# boost-highpower.net
KiCad netlist of a schematic drawn in EAGLE
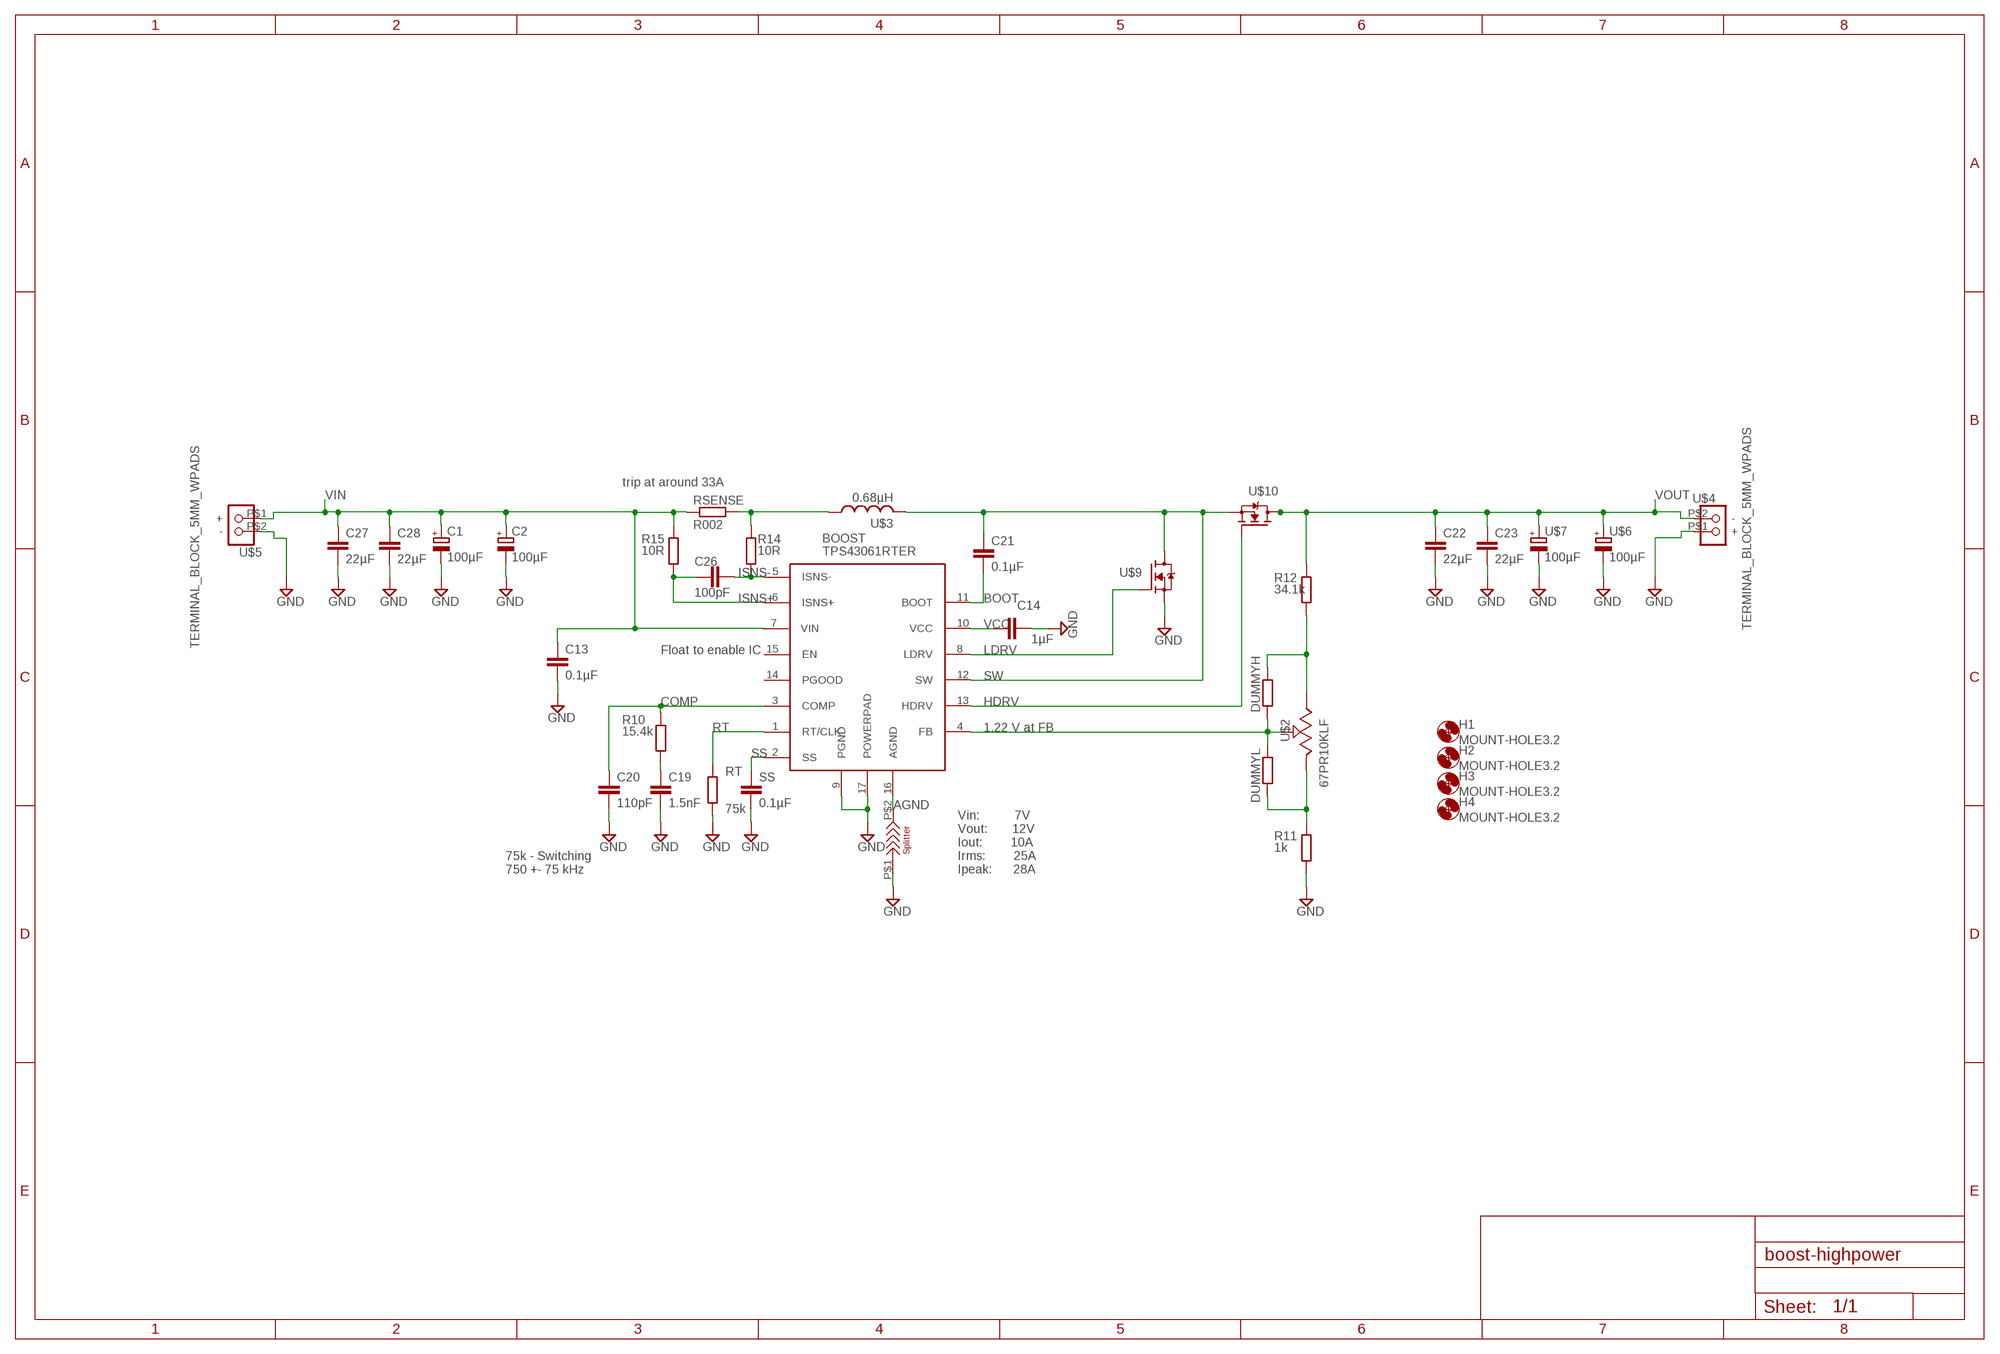
[diagram p0: schematic, sheet 1]

(export (version "E")
  (design (tool "Eeschema 10.0.6"))
  (components
    (comp (ref "BOOST")
      (value "TPS43061RTER")
      (footprint "eagle-import:QFN50P300X300X80-17N")
      (fields (field (name "MOUSER_PART_NUMBER") "595-TPS43061RTER"))
      (libsource (lib "eagle-import") (part "TPS43061RTER"))
    )
    (comp (ref "C1")
      (value "100µF")
      (footprint "eagle-import:CAPAE830X850N")
      (libsource (lib "eagle-import") (part "WCAP-ASLL-WE50V100µF"))
    )
    (comp (ref "C2")
      (value "100µF")
      (footprint "eagle-import:CAPAE830X850N")
      (libsource (lib "eagle-import") (part "WCAP-ASLL-WE50V100µF"))
    )
    (comp (ref "C13")
      (value "0.1µF")
      (footprint "eagle-import:C0805")
      (libsource (lib "eagle-import") (part "C-EUC0805"))
    )
    (comp (ref "C14")
      (value "1µF")
      (footprint "eagle-import:C0603")
      (libsource (lib "eagle-import") (part "C-EUC0603"))
    )
    (comp (ref "C19")
      (value "1.5nF")
      (footprint "eagle-import:C0603")
      (libsource (lib "eagle-import") (part "C-EUC0603"))
    )
    (comp (ref "C20")
      (value "110pF")
      (footprint "eagle-import:C0603")
      (libsource (lib "eagle-import") (part "C-EUC0603"))
    )
    (comp (ref "C21")
      (value "0.1µF")
      (footprint "eagle-import:C0805")
      (libsource (lib "eagle-import") (part "C-EUC0805"))
    )
    (comp (ref "C22")
      (value "22µF")
      (footprint "eagle-import:C0805")
      (libsource (lib "eagle-import") (part "C-EUC0805"))
    )
    (comp (ref "C23")
      (value "22µF")
      (footprint "eagle-import:C0805")
      (libsource (lib "eagle-import") (part "C-EUC0805"))
    )
    (comp (ref "C26")
      (value "100pF")
      (footprint "eagle-import:C0603")
      (libsource (lib "eagle-import") (part "C-EUC0603"))
    )
    (comp (ref "C27")
      (value "22µF")
      (footprint "eagle-import:C0805")
      (libsource (lib "eagle-import") (part "C-EUC0805"))
    )
    (comp (ref "C28")
      (value "22µF")
      (footprint "eagle-import:C0805")
      (libsource (lib "eagle-import") (part "C-EUC0805"))
    )
    (comp (ref "DUMMYH")
      (value "R-EU_R0201")
      (footprint "eagle-import:R0201")
      (libsource (lib "eagle-import") (part "R-EU_R0201"))
    )
    (comp (ref "DUMMYL")
      (value "R-EU_R0201")
      (footprint "eagle-import:R0201")
      (libsource (lib "eagle-import") (part "R-EU_R0201"))
    )
    (comp (ref "H1")
      (value "MOUNT-HOLE3.2")
      (footprint "eagle-import:3,2")
      (libsource (lib "eagle-import") (part "MOUNT-HOLE3.2"))
    )
    (comp (ref "H2")
      (value "MOUNT-HOLE3.2")
      (footprint "eagle-import:3,2")
      (libsource (lib "eagle-import") (part "MOUNT-HOLE3.2"))
    )
    (comp (ref "H3")
      (value "MOUNT-HOLE3.2")
      (footprint "eagle-import:3,2")
      (libsource (lib "eagle-import") (part "MOUNT-HOLE3.2"))
    )
    (comp (ref "H4")
      (value "MOUNT-HOLE3.2")
      (footprint "eagle-import:3,2")
      (libsource (lib "eagle-import") (part "MOUNT-HOLE3.2"))
    )
    (comp (ref "R10")
      (value "15.4k")
      (footprint "eagle-import:R0603")
      (libsource (lib "eagle-import") (part "R-EU_R0603"))
    )
    (comp (ref "R11")
      (value "1k")
      (footprint "eagle-import:R0603")
      (libsource (lib "eagle-import") (part "R-EU_R0603"))
    )
    (comp (ref "R12")
      (value "34.1k")
      (footprint "eagle-import:R0603")
      (libsource (lib "eagle-import") (part "R-EU_R0603"))
    )
    (comp (ref "R14")
      (value "10R")
      (footprint "eagle-import:R0603")
      (libsource (lib "eagle-import") (part "R-EU_R0603"))
    )
    (comp (ref "R15")
      (value "10R")
      (footprint "eagle-import:R0603")
      (libsource (lib "eagle-import") (part "R-EU_R0603"))
    )
    (comp (ref "RSENSE")
      (value "R002")
      (footprint "eagle-import:R2512W")
      (libsource (lib "eagle-import") (part "R-EU_R2512W"))
    )
    (comp (ref "RT")
      (value "75k")
      (footprint "eagle-import:R0603")
      (libsource (lib "eagle-import") (part "R-EU_R0603"))
    )
    (comp (ref "SS")
      (value "0.1µF")
      (footprint "eagle-import:C0603")
      (libsource (lib "eagle-import") (part "C-EUC0603"))
    )
    (comp (ref "U$1")
      (value "SPLITTER")
      (footprint "eagle-import:SPLITTER")
      (libsource (lib "eagle-import") (part "SPLITTER"))
    )
    (comp (ref "U$2")
      (value "67PR10KLF")
      (footprint "eagle-import:67PR10KLF")
      (libsource (lib "eagle-import") (part "67PR10KLF"))
    )
    (comp (ref "U$3")
      (value "0.68µH")
      (footprint "eagle-import:INDM135125X330N")
      (libsource (lib "eagle-import") (part "SRP1238A-XXXX"))
    )
    (comp (ref "U$4")
      (value "TERMINAL_BLOCK_5MM_WPADS")
      (footprint "eagle-import:TERMINAL_5MM_WITH_SOLDERPADS")
      (libsource (lib "eagle-import") (part "TERMINAL_BLOCK_5MM_WPADS"))
    )
    (comp (ref "U$5")
      (value "TERMINAL_BLOCK_5MM_WPADS")
      (footprint "eagle-import:TERMINAL_5MM_WITH_SOLDERPADS")
      (libsource (lib "eagle-import") (part "TERMINAL_BLOCK_5MM_WPADS"))
    )
    (comp (ref "U$6")
      (value "100µF")
      (footprint "eagle-import:CAPAE1030X1000N")
      (libsource (lib "eagle-import") (part "CAP_VZH"))
    )
    (comp (ref "U$7")
      (value "100µF")
      (footprint "eagle-import:CAPAE1030X1000N")
      (libsource (lib "eagle-import") (part "CAP_VZH"))
    )
    (comp (ref "U$9")
      (value "CSD17301Q5A")
      (footprint "eagle-import:Q5A")
      (libsource (lib "eagle-import") (part "CSD17301Q5A"))
    )
    (comp (ref "U$10")
      (value "CSD17301Q5A")
      (footprint "eagle-import:Q5A")
      (libsource (lib "eagle-import") (part "CSD17301Q5A"))
    )
  )
  (nets
    (net (code "1") (name "/AGND") (class "Default")
      (node (ref "BOOST") (pin "16") (pinfunction "AGND_16") (pintype "power_in"))
      (node (ref "U$1") (pin "P$2") (pinfunction "2_P$2") (pintype "bidirectional"))
    )
    (net (code "2") (name "/BOOT") (class "Default")
      (node (ref "BOOST") (pin "11") (pinfunction "BOOT_11") (pintype "bidirectional"))
      (node (ref "C21") (pin "2") (pinfunction "2_2") (pintype "passive"))
    )
    (net (code "3") (name "/COMP") (class "Default")
      (node (ref "BOOST") (pin "3") (pinfunction "COMP_3") (pintype "output"))
      (node (ref "C20") (pin "1") (pinfunction "1_1") (pintype "passive"))
      (node (ref "R10") (pin "2") (pinfunction "2_2") (pintype "passive"))
    )
    (net (code "4") (name "/HDRV") (class "Default")
      (node (ref "BOOST") (pin "13") (pinfunction "HDRV_13") (pintype "output"))
      (node (ref "U$10") (pin "4") (pinfunction "G_4") (pintype "passive"))
    )
    (net (code "5") (name "/ISNS+") (class "Default")
      (node (ref "BOOST") (pin "6") (pinfunction "ISNS+_6") (pintype "input"))
      (node (ref "C26") (pin "1") (pinfunction "1_1") (pintype "passive"))
      (node (ref "R15") (pin "1") (pinfunction "1_1") (pintype "passive"))
    )
    (net (code "6") (name "/ISNS-") (class "Default")
      (node (ref "BOOST") (pin "5") (pinfunction "ISNS-_5") (pintype "input"))
      (node (ref "C26") (pin "2") (pinfunction "2_2") (pintype "passive"))
      (node (ref "R14") (pin "1") (pinfunction "1_1") (pintype "passive"))
    )
    (net (code "7") (name "/LDRV") (class "Default")
      (node (ref "BOOST") (pin "8") (pinfunction "LDRV_8") (pintype "output"))
      (node (ref "U$9") (pin "4") (pinfunction "G_4") (pintype "passive"))
    )
    (net (code "8") (name "/RT") (class "Default")
      (node (ref "BOOST") (pin "1") (pinfunction "RT/CLK_1") (pintype "input"))
      (node (ref "RT") (pin "2") (pinfunction "2_2") (pintype "passive"))
    )
    (net (code "9") (name "/SS") (class "Default")
      (node (ref "BOOST") (pin "2") (pinfunction "SS_2") (pintype "bidirectional"))
      (node (ref "SS") (pin "1") (pinfunction "1_1") (pintype "passive"))
    )
    (net (code "10") (name "/SW") (class "Default")
      (node (ref "BOOST") (pin "12") (pinfunction "SW_12") (pintype "bidirectional"))
      (node (ref "C21") (pin "1") (pinfunction "1_1") (pintype "passive"))
      (node (ref "U$10") (pin "1") (pinfunction "S_1") (pintype "passive"))
      (node (ref "U$10") (pin "2") (pinfunction "S_2") (pintype "passive"))
      (node (ref "U$10") (pin "3") (pinfunction "S_3") (pintype "passive"))
      (node (ref "U$3") (pin "2") (pinfunction "2_2") (pintype "passive"))
      (node (ref "U$9") (pin "5") (pinfunction "D_5") (pintype "passive"))
      (node (ref "U$9") (pin "6") (pinfunction "D_6") (pintype "passive"))
      (node (ref "U$9") (pin "7") (pinfunction "D_7") (pintype "passive"))
      (node (ref "U$9") (pin "8") (pinfunction "D_8") (pintype "passive"))
      (node (ref "U$9") (pin "9") (pinfunction "D_9") (pintype "passive"))
    )
    (net (code "11") (name "/VCC") (class "Default")
      (node (ref "BOOST") (pin "10") (pinfunction "VCC_10") (pintype "power_in"))
      (node (ref "C14") (pin "1") (pinfunction "1_1") (pintype "passive"))
    )
    (net (code "12") (name "/VIN") (class "Default")
      (node (ref "BOOST") (pin "7") (pinfunction "VIN_7") (pintype "power_in"))
      (node (ref "C1") (pin "1") (pinfunction "+_1") (pintype "passive"))
      (node (ref "C13") (pin "1") (pinfunction "1_1") (pintype "passive"))
      (node (ref "C2") (pin "1") (pinfunction "+_1") (pintype "passive"))
      (node (ref "C27") (pin "1") (pinfunction "1_1") (pintype "passive"))
      (node (ref "C28") (pin "1") (pinfunction "1_1") (pintype "passive"))
      (node (ref "R15") (pin "2") (pinfunction "2_2") (pintype "passive"))
      (node (ref "RSENSE") (pin "1") (pinfunction "1_1") (pintype "passive"))
      (node (ref "U$5") (pin "P$1") (pinfunction "+_P$1") (pintype "bidirectional"))
    )
    (net (code "13") (name "/VOUT") (class "Default")
      (node (ref "C22") (pin "1") (pinfunction "1_1") (pintype "passive"))
      (node (ref "C23") (pin "1") (pinfunction "1_1") (pintype "passive"))
      (node (ref "R12") (pin "2") (pinfunction "2_2") (pintype "passive"))
      (node (ref "U$10") (pin "5") (pinfunction "D_5") (pintype "passive"))
      (node (ref "U$10") (pin "6") (pinfunction "D_6") (pintype "passive"))
      (node (ref "U$10") (pin "7") (pinfunction "D_7") (pintype "passive"))
      (node (ref "U$10") (pin "8") (pinfunction "D_8") (pintype "passive"))
      (node (ref "U$10") (pin "9") (pinfunction "D_9") (pintype "passive"))
      (node (ref "U$4") (pin "P$2") (pinfunction "-_P$2") (pintype "bidirectional"))
      (node (ref "U$6") (pin "1") (pinfunction "+_1") (pintype "passive"))
      (node (ref "U$7") (pin "1") (pinfunction "+_1") (pintype "passive"))
    )
    (net (code "14") (name "GND") (class "Default")
      (node (ref "BOOST") (pin "17") (pinfunction "POWERPAD_17") (pintype "power_in"))
      (node (ref "BOOST") (pin "9") (pinfunction "PGND_9") (pintype "power_in"))
      (node (ref "C1") (pin "2") (pinfunction "-_2") (pintype "passive"))
      (node (ref "C13") (pin "2") (pinfunction "2_2") (pintype "passive"))
      (node (ref "C14") (pin "2") (pinfunction "2_2") (pintype "passive"))
      (node (ref "C19") (pin "2") (pinfunction "2_2") (pintype "passive"))
      (node (ref "C2") (pin "2") (pinfunction "-_2") (pintype "passive"))
      (node (ref "C20") (pin "2") (pinfunction "2_2") (pintype "passive"))
      (node (ref "C22") (pin "2") (pinfunction "2_2") (pintype "passive"))
      (node (ref "C23") (pin "2") (pinfunction "2_2") (pintype "passive"))
      (node (ref "C27") (pin "2") (pinfunction "2_2") (pintype "passive"))
      (node (ref "C28") (pin "2") (pinfunction "2_2") (pintype "passive"))
      (node (ref "R11") (pin "1") (pinfunction "1_1") (pintype "passive"))
      (node (ref "RT") (pin "1") (pinfunction "1_1") (pintype "passive"))
      (node (ref "SS") (pin "2") (pinfunction "2_2") (pintype "passive"))
      (node (ref "U$1") (pin "P$1") (pinfunction "1_P$1") (pintype "bidirectional"))
      (node (ref "U$4") (pin "P$1") (pinfunction "+_P$1") (pintype "bidirectional"))
      (node (ref "U$5") (pin "P$2") (pinfunction "-_P$2") (pintype "bidirectional"))
      (node (ref "U$6") (pin "2") (pinfunction "-_2") (pintype "passive"))
      (node (ref "U$7") (pin "2") (pinfunction "-_2") (pintype "passive"))
      (node (ref "U$9") (pin "1") (pinfunction "S_1") (pintype "passive"))
      (node (ref "U$9") (pin "2") (pinfunction "S_2") (pintype "passive"))
      (node (ref "U$9") (pin "3") (pinfunction "S_3") (pintype "passive"))
    )
    (net (code "15") (name "Net-(BOOST-FB)") (class "Default")
      (node (ref "BOOST") (pin "4") (pinfunction "FB_4") (pintype "input"))
      (node (ref "DUMMYH") (pin "1") (pinfunction "1_1") (pintype "passive"))
      (node (ref "DUMMYL") (pin "2") (pinfunction "2_2") (pintype "passive"))
      (node (ref "U$2") (pin "P$2") (pinfunction "2_P$2") (pintype "passive"))
    )
    (net (code "16") (name "Net-(C19-Pad1)") (class "Default")
      (node (ref "C19") (pin "1") (pinfunction "1_1") (pintype "passive"))
      (node (ref "R10") (pin "1") (pinfunction "1_1") (pintype "passive"))
    )
    (net (code "17") (name "Net-(R14-Pad2)") (class "Default")
      (node (ref "R14") (pin "2") (pinfunction "2_2") (pintype "passive"))
      (node (ref "RSENSE") (pin "2") (pinfunction "2_2") (pintype "passive"))
      (node (ref "U$3") (pin "1") (pinfunction "1_1") (pintype "passive"))
    )
    (net (code "18") (name "Net-(U$2-1)") (class "Default")
      (node (ref "DUMMYL") (pin "1") (pinfunction "1_1") (pintype "passive"))
      (node (ref "R11") (pin "2") (pinfunction "2_2") (pintype "passive"))
      (node (ref "U$2") (pin "P$1") (pinfunction "1_P$1") (pintype "passive"))
    )
    (net (code "19") (name "Net-(U$2-3)") (class "Default")
      (node (ref "DUMMYH") (pin "2") (pinfunction "2_2") (pintype "passive"))
      (node (ref "R12") (pin "1") (pinfunction "1_1") (pintype "passive"))
      (node (ref "U$2") (pin "P$3") (pinfunction "3_P$3") (pintype "passive"))
    )
    (net (code "20") (name "unconnected-(BOOST-EN-Pad15)") (class "Default")
      (node (ref "BOOST") (pin "15") (pinfunction "EN_15") (pintype "input"))
    )
    (net (code "21") (name "unconnected-(BOOST-PGOOD-Pad14)") (class "Default")
      (node (ref "BOOST") (pin "14") (pinfunction "PGOOD_14") (pintype "output"))
    )
  )
)
